# edison_gpio.net
KiCad netlist of a schematic drawn in Altium Designer
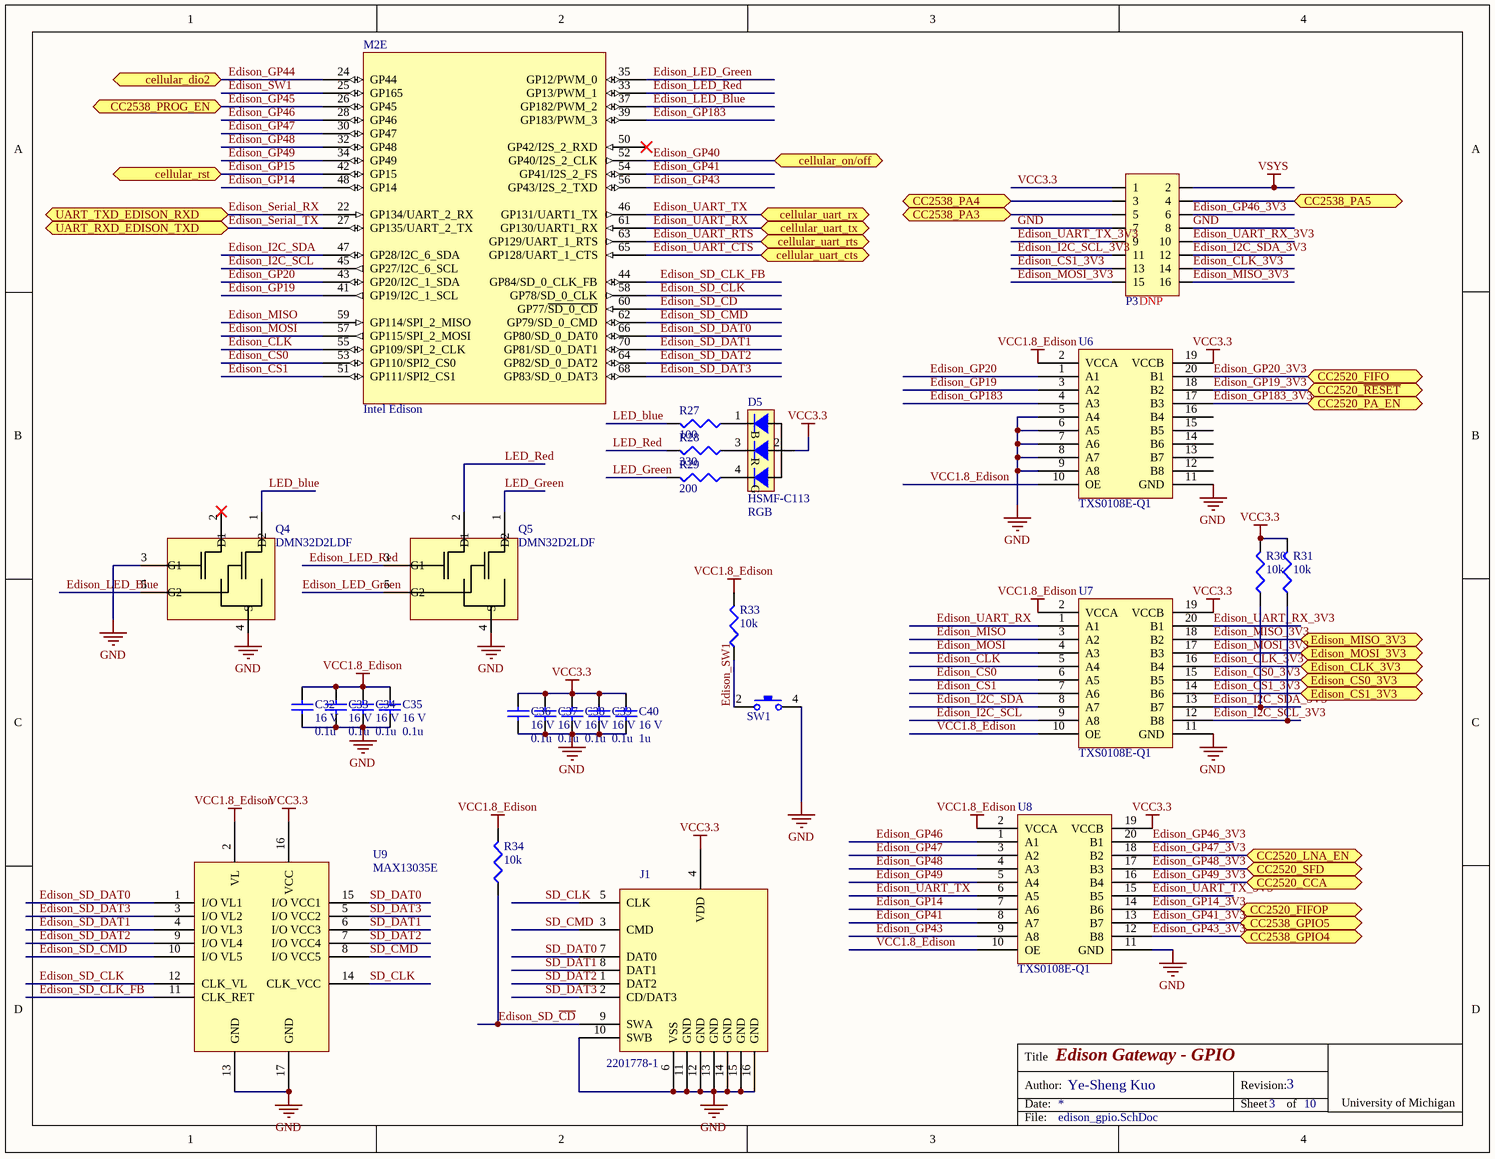
[diagram p0: edison_gpio.SchDoc]

(export (version "E")
  (design (tool "Eeschema 10.0.6"))
  (components
    (comp (ref "C32")
      (value "0.1u")
      (footprint "0402")
      (description "0.10µF ±10% 16V Ceramic Capacitor X7R 0402")
      (fields
        (field (name "VOLTAGE RATED") "16 V")
        (field (name "TOLERANCE") "10%")
        (field (name "MANUFACTURER PART NUMBER") "GRM155R71C104KA88D")
      )
      (libsource (lib "capacitors") (part "GRM155R71C104KA88D"))
    )
    (comp (ref "C33")
      (value "0.1u")
      (footprint "0402")
      (description "0.10µF ±10% 16V Ceramic Capacitor X7R 0402")
      (fields
        (field (name "VOLTAGE RATED") "16 V")
        (field (name "TOLERANCE") "10%")
        (field (name "MANUFACTURER PART NUMBER") "GRM155R71C104KA88D")
      )
      (libsource (lib "capacitors") (part "GRM155R71C104KA88D"))
    )
    (comp (ref "C34")
      (value "0.1u")
      (footprint "0402")
      (description "0.10µF ±10% 16V Ceramic Capacitor X7R 0402")
      (fields
        (field (name "VOLTAGE RATED") "16 V")
        (field (name "TOLERANCE") "10%")
        (field (name "MANUFACTURER PART NUMBER") "GRM155R71C104KA88D")
      )
      (libsource (lib "capacitors") (part "GRM155R71C104KA88D"))
    )
    (comp (ref "C35")
      (value "0.1u")
      (footprint "0402")
      (description "0.10µF ±10% 16V Ceramic Capacitor X7R 0402")
      (fields
        (field (name "VOLTAGE RATED") "16 V")
        (field (name "TOLERANCE") "10%")
        (field (name "MANUFACTURER PART NUMBER") "GRM155R71C104KA88D")
      )
      (libsource (lib "capacitors") (part "GRM155R71C104KA88D"))
    )
    (comp (ref "C36")
      (value "0.1u")
      (footprint "0402")
      (description "0.10µF ±10% 16V Ceramic Capacitor X7R 0402")
      (fields
        (field (name "VOLTAGE RATED") "16 V")
        (field (name "TOLERANCE") "10%")
        (field (name "MANUFACTURER PART NUMBER") "GRM155R71C104KA88D")
      )
      (libsource (lib "capacitors") (part "GRM155R71C104KA88D"))
    )
    (comp (ref "C37")
      (value "0.1u")
      (footprint "0402")
      (description "0.10µF ±10% 16V Ceramic Capacitor X7R 0402")
      (fields
        (field (name "VOLTAGE RATED") "16 V")
        (field (name "TOLERANCE") "10%")
        (field (name "MANUFACTURER PART NUMBER") "GRM155R71C104KA88D")
      )
      (libsource (lib "capacitors") (part "GRM155R71C104KA88D"))
    )
    (comp (ref "C38")
      (value "0.1u")
      (footprint "0402")
      (description "0.10µF ±10% 16V Ceramic Capacitor X7R 0402")
      (fields
        (field (name "VOLTAGE RATED") "16 V")
        (field (name "TOLERANCE") "10%")
        (field (name "MANUFACTURER PART NUMBER") "GRM155R71C104KA88D")
      )
      (libsource (lib "capacitors") (part "GRM155R71C104KA88D"))
    )
    (comp (ref "C39")
      (value "0.1u")
      (footprint "0402")
      (description "0.10µF ±10% 16V Ceramic Capacitor X7R 0402")
      (fields
        (field (name "VOLTAGE RATED") "16 V")
        (field (name "TOLERANCE") "10%")
        (field (name "MANUFACTURER PART NUMBER") "GRM155R71C104KA88D")
      )
      (libsource (lib "capacitors") (part "GRM155R71C104KA88D"))
    )
    (comp (ref "C40")
      (value "1u")
      (footprint "0402")
      (description "1µF ±10% 16V Ceramic Capacitor X6S 0402")
      (fields
        (field (name "VOLTAGE RATED") "16 V")
        (field (name "TOLERANCE") "10%")
        (field (name "MANUFACTURER PART NUMBER") "C1005X6S1C105K050BC")
      )
      (libsource (lib "capacitors") (part "C1005X6S1C105K050BC"))
    )
    (comp (ref "D5")
      (value "HSMF-C113")
      (footprint "HSMF")
      (fields (field (name "MANUFACTURER") "Broadcom Limited") (field (name "ALTIUM_VALUE") "RGB"))
      (libsource (lib "LED") (part "HSMF-C113"))
    )
    (comp (ref "J1")
      (value "2201778-1")
      (footprint "2201778-1")
      (description "Micro SD Slot")
      (libsource (lib "connectors") (part "2201778-1"))
    )
    (comp (ref "M2")
      (value "Intel Edison")
      (footprint "Intel Edison mating")
      (libsource (lib "Intel Edison") (part "Intel Edison"))
    )
    (comp (ref "P3")
      (value "2 x 8 header")
      (footprint "2x8 header")
      (description "100 mils standard header")
      (fields (field (name "NOTE") "DNP"))
      (libsource (lib "connectors") (part "2 x 8 header"))
    )
    (comp (ref "Q4")
      (value "DMN32D2LDF")
      (footprint "SOT-353-5")
      (description "Common Source Dual N-Channel MOSFET")
      (libsource (lib "transistors") (part "DMN32D2LDF"))
    )
    (comp (ref "Q5")
      (value "DMN32D2LDF")
      (footprint "SOT-353-5")
      (description "Common Source Dual N-Channel MOSFET")
      (libsource (lib "transistors") (part "DMN32D2LDF"))
    )
    (comp (ref "R27")
      (value "100")
      (footprint "0402")
      (description "RES SMD 100 OHM 1% 1/16W 0402")
      (fields (field (name "TOLERANCE") "1%") (field (name "POWER") "1/16 W"))
      (libsource (lib "resistors") (part "CRCW0402100RFKED"))
    )
    (comp (ref "R28")
      (value "330")
      (footprint "0402")
      (description "RES SMD 330 OHM 1% 1/16W 0402")
      (fields (field (name "TOLERANCE") "1%") (field (name "POWER") "1/16 W"))
      (libsource (lib "resistors") (part "CRCW0402330RFKED"))
    )
    (comp (ref "R29")
      (value "200")
      (footprint "0402")
      (description "RES SMD 200 OHM 1% 1/16W 0402")
      (fields (field (name "TOLERANCE") "1%") (field (name "POWER") "1/16 W"))
      (libsource (lib "resistors") (part "CRCW0402200RFKED"))
    )
    (comp (ref "R30")
      (value "10k")
      (footprint "0402")
      (description "RES SMD 10K OHM 1% 1/16W 0402")
      (fields (field (name "TOLERANCE") "1%") (field (name "POWER") "1/16 W"))
      (libsource (lib "resistors") (part "CRCW040210K0FKED"))
    )
    (comp (ref "R31")
      (value "10k")
      (footprint "0402")
      (description "RES SMD 10K OHM 1% 1/16W 0402")
      (fields (field (name "TOLERANCE") "1%") (field (name "POWER") "1/16 W"))
      (libsource (lib "resistors") (part "CRCW040210K0FKED"))
    )
    (comp (ref "R33")
      (value "10k")
      (footprint "0402")
      (description "RES SMD 10K OHM 1% 1/16W 0402")
      (fields (field (name "TOLERANCE") "1%") (field (name "POWER") "1/16 W"))
      (libsource (lib "resistors") (part "CRCW040210K0FKED"))
    )
    (comp (ref "R34")
      (value "10k")
      (footprint "0402")
      (description "RES SMD 10K OHM 1% 1/16W 0402")
      (fields (field (name "TOLERANCE") "1%") (field (name "POWER") "1/16 W"))
      (libsource (lib "resistors") (part "CRCW040210K0FKED"))
    )
    (comp (ref "SW1")
      (value "KT11P4SA2M35LFG")
      (footprint "KT11PXSA2M")
      (description "Tactile Switch SPST-NO Side Actuated Surface Mount, Right Angl")
      (libsource (lib "switches") (part "KT11P4SA2M35LFG"))
    )
    (comp (ref "U6")
      (value "TXS0108E-Q1")
      (footprint "TSSOP-20")
      (libsource (lib "level shifter") (part "TXS0108E-Q1"))
    )
    (comp (ref "U7")
      (value "TXS0108E-Q1")
      (footprint "TSSOP-20")
      (libsource (lib "level shifter") (part "TXS0108E-Q1"))
    )
    (comp (ref "U8")
      (value "TXS0108E-Q1")
      (footprint "TSSOP-20")
      (libsource (lib "level shifter") (part "TXS0108E-Q1"))
    )
    (comp (ref "U9")
      (value "MAX13035E")
      (footprint "TQFN-16")
      (description "6-Channel High-Speed Logic-Level Translators")
      (libsource (lib "level shifter") (part "MAX13035E"))
    )
  )
  (nets
    (net (code "1") (name "/CC2538_PA3") (class "Default")
      (node (ref "P3") (pin "5") (pinfunction "5_5") (pintype "passive"))
    )
    (net (code "2") (name "/CC2538_PA4") (class "Default")
      (node (ref "P3") (pin "3") (pinfunction "3_3") (pintype "passive"))
    )
    (net (code "3") (name "/CC2538_PA5") (class "Default")
      (node (ref "P3") (pin "4") (pinfunction "4_4") (pintype "passive"))
    )
    (net (code "4") (name "/Edison_CLK") (class "Default")
      (node (ref "M2") (pin "55") (pinfunction "GP109/SPI_2_CLK_55") (pintype "bidirectional"))
      (node (ref "U7") (pin "5") (pinfunction "A4_5") (pintype "passive"))
    )
    (net (code "5") (name "/Edison_CLK_3V3") (class "Default")
      (node (ref "P3") (pin "14") (pinfunction "14_14") (pintype "passive"))
      (node (ref "U7") (pin "16") (pinfunction "B4_16") (pintype "passive"))
    )
    (net (code "6") (name "/Edison_CS0") (class "Default")
      (node (ref "M2") (pin "53") (pinfunction "GP110/SPI2_CS0_53") (pintype "bidirectional"))
      (node (ref "U7") (pin "6") (pinfunction "A5_6") (pintype "passive"))
    )
    (net (code "7") (name "/Edison_CS0_3V3") (class "Default")
      (node (ref "U7") (pin "15") (pinfunction "B5_15") (pintype "passive"))
    )
    (net (code "8") (name "/Edison_CS1") (class "Default")
      (node (ref "M2") (pin "51") (pinfunction "GP111/SPI2_CS1_51") (pintype "bidirectional"))
      (node (ref "U7") (pin "7") (pinfunction "A6_7") (pintype "passive"))
    )
    (net (code "9") (name "/Edison_CS1_3V3") (class "Default")
      (node (ref "P3") (pin "13") (pinfunction "13_13") (pintype "passive"))
      (node (ref "U7") (pin "14") (pinfunction "B6_14") (pintype "passive"))
    )
    (net (code "10") (name "/Edison_GP14") (class "Default")
      (node (ref "M2") (pin "48") (pinfunction "GP14_48") (pintype "bidirectional"))
      (node (ref "U8") (pin "7") (pinfunction "A6_7") (pintype "passive"))
    )
    (net (code "11") (name "/Edison_GP14_3V3") (class "Default")
      (node (ref "U8") (pin "14") (pinfunction "B6_14") (pintype "passive"))
    )
    (net (code "12") (name "/Edison_GP15") (class "Default")
      (node (ref "M2") (pin "42") (pinfunction "GP15_42") (pintype "bidirectional"))
    )
    (net (code "13") (name "/Edison_GP19") (class "Default")
      (node (ref "M2") (pin "41") (pinfunction "GP19/I2C_1_SCL_41") (pintype "output"))
      (node (ref "U6") (pin "3") (pinfunction "A2_3") (pintype "passive"))
    )
    (net (code "14") (name "/Edison_GP19_3V3") (class "Default")
      (node (ref "U6") (pin "18") (pinfunction "B2_18") (pintype "passive"))
    )
    (net (code "15") (name "/Edison_GP20") (class "Default")
      (node (ref "M2") (pin "43") (pinfunction "GP20/I2C_1_SDA_43") (pintype "bidirectional"))
      (node (ref "U6") (pin "1") (pinfunction "A1_1") (pintype "passive"))
    )
    (net (code "16") (name "/Edison_GP20_3V3") (class "Default")
      (node (ref "U6") (pin "20") (pinfunction "B1_20") (pintype "passive"))
    )
    (net (code "17") (name "/Edison_GP40") (class "Default")
      (node (ref "M2") (pin "52") (pinfunction "GP40/I2S_2_CLK_52") (pintype "output"))
    )
    (net (code "18") (name "/Edison_GP41") (class "Default")
      (node (ref "M2") (pin "54") (pinfunction "GP41/I2S_2_FS_54") (pintype "bidirectional"))
      (node (ref "U8") (pin "8") (pinfunction "A7_8") (pintype "passive"))
    )
    (net (code "19") (name "/Edison_GP41_3V3") (class "Default")
      (node (ref "U8") (pin "13") (pinfunction "B7_13") (pintype "passive"))
    )
    (net (code "20") (name "/Edison_GP43") (class "Default")
      (node (ref "M2") (pin "56") (pinfunction "GP43/I2S_2_TXD_56") (pintype "bidirectional"))
      (node (ref "U8") (pin "9") (pinfunction "A8_9") (pintype "passive"))
    )
    (net (code "21") (name "/Edison_GP43_3V3") (class "Default")
      (node (ref "U8") (pin "12") (pinfunction "B8_12") (pintype "passive"))
    )
    (net (code "22") (name "/Edison_GP44") (class "Default")
      (node (ref "M2") (pin "24") (pinfunction "GP44_24") (pintype "bidirectional"))
    )
    (net (code "23") (name "/Edison_GP45") (class "Default")
      (node (ref "M2") (pin "26") (pinfunction "GP45_26") (pintype "bidirectional"))
    )
    (net (code "24") (name "/Edison_GP46") (class "Default")
      (node (ref "M2") (pin "28") (pinfunction "GP46_28") (pintype "bidirectional"))
      (node (ref "U8") (pin "1") (pinfunction "A1_1") (pintype "passive"))
    )
    (net (code "25") (name "/Edison_GP46_3V3") (class "Default")
      (node (ref "P3") (pin "6") (pinfunction "6_6") (pintype "passive"))
      (node (ref "U8") (pin "20") (pinfunction "B1_20") (pintype "passive"))
    )
    (net (code "26") (name "/Edison_GP47") (class "Default")
      (node (ref "M2") (pin "30") (pinfunction "GP47_30") (pintype "bidirectional"))
      (node (ref "U8") (pin "3") (pinfunction "A2_3") (pintype "passive"))
    )
    (net (code "27") (name "/Edison_GP47_3V3") (class "Default")
      (node (ref "U8") (pin "18") (pinfunction "B2_18") (pintype "passive"))
    )
    (net (code "28") (name "/Edison_GP48") (class "Default")
      (node (ref "M2") (pin "32") (pinfunction "GP48_32") (pintype "bidirectional"))
      (node (ref "U8") (pin "4") (pinfunction "A3_4") (pintype "passive"))
    )
    (net (code "29") (name "/Edison_GP48_3V3") (class "Default")
      (node (ref "U8") (pin "17") (pinfunction "B3_17") (pintype "passive"))
    )
    (net (code "30") (name "/Edison_GP49") (class "Default")
      (node (ref "M2") (pin "34") (pinfunction "GP49_34") (pintype "bidirectional"))
      (node (ref "U8") (pin "5") (pinfunction "A4_5") (pintype "passive"))
    )
    (net (code "31") (name "/Edison_GP49_3V3") (class "Default")
      (node (ref "U8") (pin "16") (pinfunction "B4_16") (pintype "passive"))
    )
    (net (code "32") (name "/Edison_GP183") (class "Default")
      (node (ref "M2") (pin "39") (pinfunction "GP183/PWM_3_39") (pintype "bidirectional"))
      (node (ref "U6") (pin "4") (pinfunction "A3_4") (pintype "passive"))
    )
    (net (code "33") (name "/Edison_GP183_3V3") (class "Default")
      (node (ref "U6") (pin "17") (pinfunction "B3_17") (pintype "passive"))
    )
    (net (code "34") (name "/Edison_I2C_SCL") (class "Default")
      (node (ref "M2") (pin "45") (pinfunction "GP27/I2C_6_SCL_45") (pintype "output"))
      (node (ref "U7") (pin "9") (pinfunction "A8_9") (pintype "passive"))
    )
    (net (code "35") (name "/Edison_I2C_SCL_3V3") (class "Default")
      (node (ref "P3") (pin "11") (pinfunction "11_11") (pintype "passive"))
      (node (ref "R31") (pin "2") (pintype "passive"))
      (node (ref "U7") (pin "12") (pinfunction "B8_12") (pintype "passive"))
    )
    (net (code "36") (name "/Edison_I2C_SDA") (class "Default")
      (node (ref "M2") (pin "47") (pinfunction "GP28/I2C_6_SDA_47") (pintype "bidirectional"))
      (node (ref "U7") (pin "8") (pinfunction "A7_8") (pintype "passive"))
    )
    (net (code "37") (name "/Edison_I2C_SDA_3V3") (class "Default")
      (node (ref "P3") (pin "12") (pinfunction "12_12") (pintype "passive"))
      (node (ref "R30") (pin "2") (pintype "passive"))
      (node (ref "U7") (pin "13") (pinfunction "B7_13") (pintype "passive"))
    )
    (net (code "38") (name "/Edison_LED_Blue") (class "Default")
      (node (ref "M2") (pin "37") (pinfunction "GP182/PWM_2_37") (pintype "bidirectional"))
      (node (ref "Q4") (pin "5") (pinfunction "G2_5") (pintype "passive"))
    )
    (net (code "39") (name "/Edison_LED_Green") (class "Default")
      (node (ref "M2") (pin "35") (pinfunction "GP12/PWM_0_35") (pintype "bidirectional"))
      (node (ref "Q5") (pin "5") (pinfunction "G2_5") (pintype "passive"))
    )
    (net (code "40") (name "/Edison_LED_Red") (class "Default")
      (node (ref "M2") (pin "33") (pinfunction "GP13/PWM_1_33") (pintype "bidirectional"))
      (node (ref "Q5") (pin "3") (pinfunction "G1_3") (pintype "passive"))
    )
    (net (code "41") (name "/Edison_MISO") (class "Default")
      (node (ref "M2") (pin "59") (pinfunction "GP114/SPI_2_MISO_59") (pintype "input"))
      (node (ref "U7") (pin "3") (pinfunction "A2_3") (pintype "passive"))
    )
    (net (code "42") (name "/Edison_MISO_3V3") (class "Default")
      (node (ref "P3") (pin "16") (pinfunction "16_16") (pintype "passive"))
      (node (ref "U7") (pin "18") (pinfunction "B2_18") (pintype "passive"))
    )
    (net (code "43") (name "/Edison_MOSI") (class "Default")
      (node (ref "M2") (pin "57") (pinfunction "GP115/SPI_2_MOSI_57") (pintype "output"))
      (node (ref "U7") (pin "4") (pinfunction "A3_4") (pintype "passive"))
    )
    (net (code "44") (name "/Edison_MOSI_3V3") (class "Default")
      (node (ref "P3") (pin "15") (pinfunction "15_15") (pintype "passive"))
      (node (ref "U7") (pin "17") (pinfunction "B3_17") (pintype "passive"))
    )
    (net (code "45") (name "/Edison_SD_CLK") (class "Default")
      (node (ref "M2") (pin "58") (pinfunction "GP78/SD_0_CLK_58") (pintype "output"))
      (node (ref "U9") (pin "12") (pinfunction "CLK_VL_12") (pintype "passive"))
    )
    (net (code "46") (name "/Edison_SD_CLK_FB") (class "Default")
      (node (ref "M2") (pin "44") (pinfunction "GP84/SD_0_CLK_FB_44") (pintype "bidirectional"))
      (node (ref "U9") (pin "11") (pinfunction "CLK_RET_11") (pintype "passive"))
    )
    (net (code "47") (name "/Edison_SD_CMD") (class "Default")
      (node (ref "M2") (pin "62") (pinfunction "GP79/SD_0_CMD_62") (pintype "bidirectional"))
      (node (ref "U9") (pin "10") (pinfunction "I/O_VL5_10") (pintype "passive"))
    )
    (net (code "48") (name "/Edison_SD_DAT0") (class "Default")
      (node (ref "M2") (pin "66") (pinfunction "GP80/SD_0_DAT0_66") (pintype "bidirectional"))
      (node (ref "U9") (pin "1") (pinfunction "I/O_VL1_1") (pintype "passive"))
    )
    (net (code "49") (name "/Edison_SD_DAT1") (class "Default")
      (node (ref "M2") (pin "70") (pinfunction "GP81/SD_0_DAT1_70") (pintype "bidirectional"))
      (node (ref "U9") (pin "4") (pinfunction "I/O_VL3_4") (pintype "passive"))
    )
    (net (code "50") (name "/Edison_SD_DAT2") (class "Default")
      (node (ref "M2") (pin "64") (pinfunction "GP82/SD_0_DAT2_64") (pintype "bidirectional"))
      (node (ref "U9") (pin "9") (pinfunction "I/O_VL4_9") (pintype "passive"))
    )
    (net (code "51") (name "/Edison_SD_DAT3") (class "Default")
      (node (ref "M2") (pin "68") (pinfunction "GP83/SD_0_DAT3_68") (pintype "bidirectional"))
      (node (ref "U9") (pin "3") (pinfunction "I/O_VL2_3") (pintype "passive"))
    )
    (net (code "52") (name "/Edison_SD_~{CD}") (class "Default")
      (node (ref "J1") (pin "9") (pinfunction "SWA_9") (pintype "passive"))
      (node (ref "M2") (pin "60") (pinfunction "GP77/~{SD_0_CD}_60") (pintype "input"))
      (node (ref "R34") (pin "2") (pintype "passive"))
    )
    (net (code "53") (name "/Edison_SW1") (class "Default")
      (node (ref "M2") (pin "25") (pinfunction "GP165_25") (pintype "bidirectional"))
      (node (ref "R33") (pin "2") (pintype "passive"))
      (node (ref "SW1") (pin "2") (pinfunction "2_2") (pintype "passive"))
    )
    (net (code "54") (name "/Edison_Serial_RX") (class "Default")
      (node (ref "M2") (pin "22") (pinfunction "GP134/UART_2_RX_22") (pintype "input"))
    )
    (net (code "55") (name "/Edison_Serial_TX") (class "Default")
      (node (ref "M2") (pin "27") (pinfunction "GP135/UART_2_TX_27") (pintype "bidirectional"))
    )
    (net (code "56") (name "/Edison_UART_CTS") (class "Default")
      (node (ref "M2") (pin "65") (pinfunction "GP128/UART_1_CTS_65") (pintype "input"))
    )
    (net (code "57") (name "/Edison_UART_RTS") (class "Default")
      (node (ref "M2") (pin "63") (pinfunction "GP129/UART_1_RTS_63") (pintype "output"))
    )
    (net (code "58") (name "/Edison_UART_RX") (class "Default")
      (node (ref "M2") (pin "61") (pinfunction "GP130/UART1_RX_61") (pintype "input"))
      (node (ref "U7") (pin "1") (pinfunction "A1_1") (pintype "passive"))
    )
    (net (code "59") (name "/Edison_UART_RX_3V3") (class "Default")
      (node (ref "P3") (pin "10") (pinfunction "10_10") (pintype "passive"))
      (node (ref "U7") (pin "20") (pinfunction "B1_20") (pintype "passive"))
    )
    (net (code "60") (name "/Edison_UART_TX") (class "Default")
      (node (ref "M2") (pin "46") (pinfunction "GP131/UART1_TX_46") (pintype "output"))
      (node (ref "U8") (pin "6") (pinfunction "A5_6") (pintype "passive"))
    )
    (net (code "61") (name "/Edison_UART_TX_3V3") (class "Default")
      (node (ref "P3") (pin "9") (pinfunction "9_9") (pintype "passive"))
      (node (ref "U8") (pin "15") (pinfunction "B5_15") (pintype "passive"))
    )
    (net (code "62") (name "/LED_Green") (class "Default")
      (node (ref "Q5") (pin "1") (pinfunction "D2_1") (pintype "passive"))
      (node (ref "R29") (pin "1") (pintype "passive"))
    )
    (net (code "63") (name "/LED_Red") (class "Default")
      (node (ref "Q5") (pin "2") (pinfunction "D1_2") (pintype "passive"))
      (node (ref "R28") (pin "1") (pintype "passive"))
    )
    (net (code "64") (name "/LED_blue") (class "Default")
      (node (ref "Q4") (pin "1") (pinfunction "D2_1") (pintype "passive"))
      (node (ref "R27") (pin "1") (pintype "passive"))
    )
    (net (code "65") (name "/SD_CLK") (class "Default")
      (node (ref "J1") (pin "5") (pinfunction "CLK_5") (pintype "passive"))
      (node (ref "U9") (pin "14") (pinfunction "CLK_VCC_14") (pintype "passive"))
    )
    (net (code "66") (name "/SD_CMD") (class "Default")
      (node (ref "J1") (pin "3") (pinfunction "CMD_3") (pintype "passive"))
      (node (ref "U9") (pin "8") (pinfunction "I/O_VCC5_8") (pintype "passive"))
    )
    (net (code "67") (name "/SD_DAT0") (class "Default")
      (node (ref "J1") (pin "7") (pinfunction "DAT0_7") (pintype "passive"))
      (node (ref "U9") (pin "15") (pinfunction "I/O_VCC1_15") (pintype "passive"))
    )
    (net (code "68") (name "/SD_DAT1") (class "Default")
      (node (ref "J1") (pin "8") (pinfunction "DAT1_8") (pintype "passive"))
      (node (ref "U9") (pin "6") (pinfunction "I/O_VCC3_6") (pintype "passive"))
    )
    (net (code "69") (name "/SD_DAT2") (class "Default")
      (node (ref "J1") (pin "1") (pinfunction "DAT2_1") (pintype "passive"))
      (node (ref "U9") (pin "7") (pinfunction "I/O_VCC4_7") (pintype "passive"))
    )
    (net (code "70") (name "/SD_DAT3") (class "Default")
      (node (ref "J1") (pin "2") (pinfunction "CD/DAT3_2") (pintype "passive"))
      (node (ref "U9") (pin "5") (pinfunction "I/O_VCC2_5") (pintype "passive"))
    )
    (net (code "71") (name "GND") (class "Default")
      (node (ref "C32") (pin "2") (pintype "passive"))
      (node (ref "C33") (pin "2") (pintype "passive"))
      (node (ref "C34") (pin "2") (pintype "passive"))
      (node (ref "C35") (pin "2") (pintype "passive"))
      (node (ref "C36") (pin "2") (pintype "passive"))
      (node (ref "C37") (pin "2") (pintype "passive"))
      (node (ref "C38") (pin "2") (pintype "passive"))
      (node (ref "C39") (pin "2") (pintype "passive"))
      (node (ref "C40") (pin "2") (pintype "passive"))
      (node (ref "J1") (pin "10") (pinfunction "SWB_10") (pintype "passive"))
      (node (ref "J1") (pin "11") (pinfunction "GND_11") (pintype "passive"))
      (node (ref "J1") (pin "12") (pinfunction "GND_12") (pintype "passive"))
      (node (ref "J1") (pin "13") (pinfunction "GND_13") (pintype "passive"))
      (node (ref "J1") (pin "14") (pinfunction "GND_14") (pintype "passive"))
      (node (ref "J1") (pin "15") (pinfunction "GND_15") (pintype "passive"))
      (node (ref "J1") (pin "16") (pinfunction "GND_16") (pintype "passive"))
      (node (ref "J1") (pin "6") (pinfunction "VSS_6") (pintype "passive"))
      (node (ref "P3") (pin "7") (pinfunction "7_7") (pintype "passive"))
      (node (ref "P3") (pin "8") (pinfunction "8_8") (pintype "passive"))
      (node (ref "Q4") (pin "3") (pinfunction "G1_3") (pintype "passive"))
      (node (ref "Q4") (pin "4") (pinfunction "S_4") (pintype "passive"))
      (node (ref "Q5") (pin "4") (pinfunction "S_4") (pintype "passive"))
      (node (ref "SW1") (pin "4") (pinfunction "4_4") (pintype "passive"))
      (node (ref "U6") (pin "11") (pinfunction "GND_11") (pintype "passive"))
      (node (ref "U6") (pin "5") (pinfunction "A4_5") (pintype "passive"))
      (node (ref "U6") (pin "6") (pinfunction "A5_6") (pintype "passive"))
      (node (ref "U6") (pin "7") (pinfunction "A6_7") (pintype "passive"))
      (node (ref "U6") (pin "8") (pinfunction "A7_8") (pintype "passive"))
      (node (ref "U6") (pin "9") (pinfunction "A8_9") (pintype "passive"))
      (node (ref "U7") (pin "11") (pinfunction "GND_11") (pintype "passive"))
      (node (ref "U8") (pin "11") (pinfunction "GND_11") (pintype "passive"))
      (node (ref "U9") (pin "13") (pinfunction "GND_13") (pintype "passive"))
      (node (ref "U9") (pin "17") (pinfunction "GND_17") (pintype "passive"))
    )
    (net (code "72") (name "Net-(D5-Pad1)") (class "Default")
      (node (ref "D5") (pin "1") (pintype "passive"))
      (node (ref "R27") (pin "2") (pintype "passive"))
    )
    (net (code "73") (name "Net-(D5-Pad3)") (class "Default")
      (node (ref "D5") (pin "3") (pinfunction "3_3") (pintype "passive"))
      (node (ref "R28") (pin "2") (pintype "passive"))
    )
    (net (code "74") (name "Net-(D5-Pad4)") (class "Default")
      (node (ref "D5") (pin "4") (pinfunction "4_4") (pintype "passive"))
      (node (ref "R29") (pin "2") (pintype "passive"))
    )
    (net (code "75") (name "VCC1.8_Edison") (class "Default")
      (node (ref "C32") (pin "1") (pintype "passive"))
      (node (ref "C33") (pin "1") (pintype "passive"))
      (node (ref "C34") (pin "1") (pintype "passive"))
      (node (ref "C35") (pin "1") (pintype "passive"))
      (node (ref "R33") (pin "1") (pintype "passive"))
      (node (ref "R34") (pin "1") (pintype "passive"))
      (node (ref "U6") (pin "10") (pinfunction "OE_10") (pintype "passive"))
      (node (ref "U6") (pin "2") (pinfunction "VCCA_2") (pintype "passive"))
      (node (ref "U7") (pin "10") (pinfunction "OE_10") (pintype "passive"))
      (node (ref "U7") (pin "2") (pinfunction "VCCA_2") (pintype "passive"))
      (node (ref "U8") (pin "10") (pinfunction "OE_10") (pintype "passive"))
      (node (ref "U8") (pin "2") (pinfunction "VCCA_2") (pintype "passive"))
      (node (ref "U9") (pin "2") (pinfunction "VL_2") (pintype "passive"))
    )
    (net (code "76") (name "VCC3.3") (class "Default")
      (node (ref "C36") (pin "1") (pintype "passive"))
      (node (ref "C37") (pin "1") (pintype "passive"))
      (node (ref "C38") (pin "1") (pintype "passive"))
      (node (ref "C39") (pin "1") (pintype "passive"))
      (node (ref "C40") (pin "1") (pintype "passive"))
      (node (ref "D5") (pin "2") (pintype "passive"))
      (node (ref "J1") (pin "4") (pinfunction "VDD_4") (pintype "passive"))
      (node (ref "P3") (pin "1") (pinfunction "1_1") (pintype "passive"))
      (node (ref "R30") (pin "1") (pintype "passive"))
      (node (ref "R31") (pin "1") (pintype "passive"))
      (node (ref "U6") (pin "19") (pinfunction "VCCB_19") (pintype "passive"))
      (node (ref "U7") (pin "19") (pinfunction "VCCB_19") (pintype "passive"))
      (node (ref "U8") (pin "19") (pinfunction "VCCB_19") (pintype "passive"))
      (node (ref "U9") (pin "16") (pinfunction "VCC_16") (pintype "passive"))
    )
    (net (code "77") (name "VSYS") (class "Default")
      (node (ref "P3") (pin "2") (pinfunction "2_2") (pintype "passive"))
    )
    (net (code "78") (name "unconnected-(M2E-GP42{slash}I2S_2_RXD-Pad50)") (class "Default")
      (node (ref "M2") (pin "50") (pinfunction "GP42/I2S_2_RXD_50") (pintype "input+no_connect"))
    )
    (net (code "79") (name "unconnected-(Q4-D1-Pad2)") (class "Default")
      (node (ref "Q4") (pin "2") (pinfunction "D1_2") (pintype "passive+no_connect"))
    )
    (net (code "80") (name "unconnected-(U6-B4-Pad16)") (class "Default")
      (node (ref "U6") (pin "16") (pinfunction "B4_16") (pintype "passive"))
    )
    (net (code "81") (name "unconnected-(U6-B5-Pad15)") (class "Default")
      (node (ref "U6") (pin "15") (pinfunction "B5_15") (pintype "passive"))
    )
    (net (code "82") (name "unconnected-(U6-B6-Pad14)") (class "Default")
      (node (ref "U6") (pin "14") (pinfunction "B6_14") (pintype "passive"))
    )
    (net (code "83") (name "unconnected-(U6-B7-Pad13)") (class "Default")
      (node (ref "U6") (pin "13") (pinfunction "B7_13") (pintype "passive"))
    )
    (net (code "84") (name "unconnected-(U6-B8-Pad12)") (class "Default")
      (node (ref "U6") (pin "12") (pinfunction "B8_12") (pintype "passive"))
    )
  )
)
